# Pixie84Servo.net
KiCad netlist of a schematic drawn in EAGLE
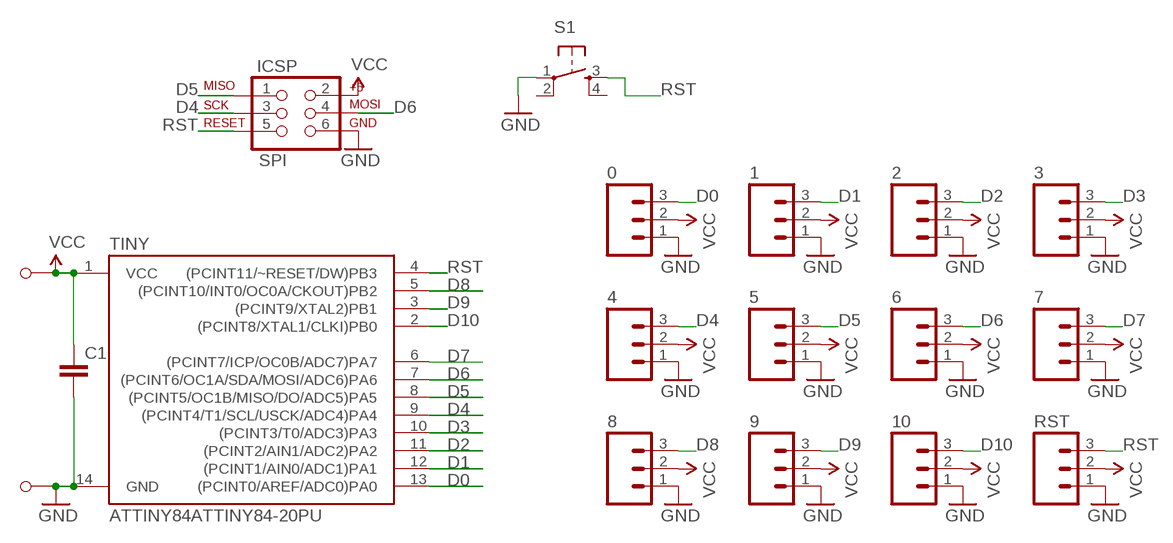
[diagram p0: schematic, sheet 1]

(export (version "E")
  (design (tool "Eeschema 10.0.6"))
  (components
    (comp (ref "0")
      (value "M03PTH")
      (footprint "eagle-import:1X03")
      (libsource (lib "eagle-import") (part "M03PTH"))
    )
    (comp (ref "1")
      (value "M03PTH")
      (footprint "eagle-import:1X03")
      (libsource (lib "eagle-import") (part "M03PTH"))
    )
    (comp (ref "2")
      (value "M03PTH")
      (footprint "eagle-import:1X03")
      (libsource (lib "eagle-import") (part "M03PTH"))
    )
    (comp (ref "3")
      (value "M03PTH")
      (footprint "eagle-import:1X03")
      (libsource (lib "eagle-import") (part "M03PTH"))
    )
    (comp (ref "4")
      (value "M03PTH")
      (footprint "eagle-import:1X03")
      (libsource (lib "eagle-import") (part "M03PTH"))
    )
    (comp (ref "5")
      (value "M03PTH")
      (footprint "eagle-import:1X03")
      (libsource (lib "eagle-import") (part "M03PTH"))
    )
    (comp (ref "6")
      (value "M03PTH")
      (footprint "eagle-import:1X03")
      (libsource (lib "eagle-import") (part "M03PTH"))
    )
    (comp (ref "7")
      (value "M03PTH")
      (footprint "eagle-import:1X03")
      (libsource (lib "eagle-import") (part "M03PTH"))
    )
    (comp (ref "8")
      (value "M03PTH")
      (footprint "eagle-import:1X03")
      (libsource (lib "eagle-import") (part "M03PTH"))
    )
    (comp (ref "9")
      (value "M03PTH")
      (footprint "eagle-import:1X03")
      (libsource (lib "eagle-import") (part "M03PTH"))
    )
    (comp (ref "10")
      (value "M03PTH")
      (footprint "eagle-import:1X03")
      (libsource (lib "eagle-import") (part "M03PTH"))
    )
    (comp (ref "C1")
      (value "CAPPTH")
      (footprint "eagle-import:CAP-PTH-SMALL")
      (libsource (lib "eagle-import") (part "CAPPTH"))
    )
    (comp (ref "ICSP")
      (value "SPI")
      (footprint "eagle-import:2X3-NS")
      (libsource (lib "eagle-import") (part "AVR_SPI_PRG_6LABELED"))
    )
    (comp (ref "RST")
      (value "M03PTH")
      (footprint "eagle-import:1X03")
      (libsource (lib "eagle-import") (part "M03PTH"))
    )
    (comp (ref "S1")
      (value "TAC_SWITCHPTH")
      (footprint "eagle-import:TACTILE-PTH")
      (libsource (lib "eagle-import") (part "TAC_SWITCHPTH"))
    )
    (comp (ref "TINY")
      (value "ATTINY84ATTINY84-20PU")
      (footprint "eagle-import:DIL14")
      (libsource (lib "eagle-import") (part "ATTINY84ATTINY84-20PU"))
    )
    (comp (ref "U$1")
      (value "M1")
      (footprint "eagle-import:M1_NO_STRAIN")
      (libsource (lib "eagle-import") (part "M1"))
    )
    (comp (ref "U$2")
      (value "M1")
      (footprint "eagle-import:M1_NO_STRAIN")
      (libsource (lib "eagle-import") (part "M1"))
    )
  )
  (nets
    (net (code "1") (name "/D0") (class "Default")
      (node (ref "0") (pin "3") (pinfunction "3_3") (pintype "passive"))
      (node (ref "TINY") (pin "13") (pinfunction "(PCINT0/AREF/ADC0)PA0_13") (pintype "bidirectional"))
    )
    (net (code "2") (name "/D1") (class "Default")
      (node (ref "1") (pin "3") (pinfunction "3_3") (pintype "passive"))
      (node (ref "TINY") (pin "12") (pinfunction "(PCINT1/AIN0/ADC1)PA1_12") (pintype "bidirectional"))
    )
    (net (code "3") (name "/D2") (class "Default")
      (node (ref "2") (pin "3") (pinfunction "3_3") (pintype "passive"))
      (node (ref "TINY") (pin "11") (pinfunction "(PCINT2/AIN1/ADC2)PA2_11") (pintype "bidirectional"))
    )
    (net (code "4") (name "/D3") (class "Default")
      (node (ref "3") (pin "3") (pinfunction "3_3") (pintype "passive"))
      (node (ref "TINY") (pin "10") (pinfunction "(PCINT3/T0/ADC3)PA3_10") (pintype "bidirectional"))
    )
    (net (code "5") (name "/D4") (class "Default")
      (node (ref "4") (pin "3") (pinfunction "3_3") (pintype "passive"))
      (node (ref "ICSP") (pin "3") (pinfunction "SCK_3") (pintype "passive"))
      (node (ref "TINY") (pin "9") (pinfunction "(PCINT4/T1/SCL/USCK/ADC4)PA4_9") (pintype "bidirectional"))
    )
    (net (code "6") (name "/D5") (class "Default")
      (node (ref "5") (pin "3") (pinfunction "3_3") (pintype "passive"))
      (node (ref "ICSP") (pin "1") (pinfunction "MISO_1") (pintype "passive"))
      (node (ref "TINY") (pin "8") (pinfunction "(PCINT5/OC1B/MISO/DO/ADC5)PA5_8") (pintype "bidirectional"))
    )
    (net (code "7") (name "/D6") (class "Default")
      (node (ref "6") (pin "3") (pinfunction "3_3") (pintype "passive"))
      (node (ref "ICSP") (pin "4") (pinfunction "MOSI_4") (pintype "passive"))
      (node (ref "TINY") (pin "7") (pinfunction "(PCINT6/OC1A/SDA/MOSI/ADC6)PA6_7") (pintype "bidirectional"))
    )
    (net (code "8") (name "/D7") (class "Default")
      (node (ref "7") (pin "3") (pinfunction "3_3") (pintype "passive"))
      (node (ref "TINY") (pin "6") (pinfunction "(PCINT7/ICP/OC0B/ADC7)PA7_6") (pintype "bidirectional"))
    )
    (net (code "9") (name "/D8") (class "Default")
      (node (ref "8") (pin "3") (pinfunction "3_3") (pintype "passive"))
      (node (ref "TINY") (pin "5") (pinfunction "(PCINT10/INT0/OC0A/CKOUT)PB2_5") (pintype "bidirectional"))
    )
    (net (code "10") (name "/D9") (class "Default")
      (node (ref "9") (pin "3") (pinfunction "3_3") (pintype "passive"))
      (node (ref "TINY") (pin "3") (pinfunction "(PCINT9/XTAL2)PB1_3") (pintype "bidirectional"))
    )
    (net (code "11") (name "/D10") (class "Default")
      (node (ref "10") (pin "3") (pinfunction "3_3") (pintype "passive"))
      (node (ref "TINY") (pin "2") (pinfunction "(PCINT8/XTAL1/CLKI)PB0_2") (pintype "bidirectional"))
    )
    (net (code "12") (name "/RST") (class "Default")
      (node (ref "ICSP") (pin "5") (pinfunction "RST_5") (pintype "passive"))
      (node (ref "RST") (pin "3") (pinfunction "3_3") (pintype "passive"))
      (node (ref "S1") (pin "3") (pinfunction "3_3") (pintype "passive"))
      (node (ref "TINY") (pin "4") (pinfunction "(PCINT11/~{RESET/DW})PB3_4") (pintype "bidirectional"))
    )
    (net (code "13") (name "GND") (class "Default")
      (node (ref "0") (pin "1") (pinfunction "1_1") (pintype "passive"))
      (node (ref "1") (pin "1") (pinfunction "1_1") (pintype "passive"))
      (node (ref "10") (pin "1") (pinfunction "1_1") (pintype "passive"))
      (node (ref "2") (pin "1") (pinfunction "1_1") (pintype "passive"))
      (node (ref "3") (pin "1") (pinfunction "1_1") (pintype "passive"))
      (node (ref "4") (pin "1") (pinfunction "1_1") (pintype "passive"))
      (node (ref "5") (pin "1") (pinfunction "1_1") (pintype "passive"))
      (node (ref "6") (pin "1") (pinfunction "1_1") (pintype "passive"))
      (node (ref "7") (pin "1") (pinfunction "1_1") (pintype "passive"))
      (node (ref "8") (pin "1") (pinfunction "1_1") (pintype "passive"))
      (node (ref "9") (pin "1") (pinfunction "1_1") (pintype "passive"))
      (node (ref "C1") (pin "2") (pinfunction "2_2") (pintype "passive"))
      (node (ref "ICSP") (pin "6") (pinfunction "GND_6") (pintype "passive"))
      (node (ref "RST") (pin "1") (pinfunction "1_1") (pintype "passive"))
      (node (ref "S1") (pin "1") (pinfunction "1_1") (pintype "passive"))
      (node (ref "TINY") (pin "14") (pinfunction "GND_14") (pintype "bidirectional"))
      (node (ref "U$2") (pin "P$1") (pinfunction "P$1_P$1") (pintype "bidirectional"))
    )
    (net (code "14") (name "VCC") (class "Default")
      (node (ref "0") (pin "2") (pinfunction "2_2") (pintype "passive"))
      (node (ref "1") (pin "2") (pinfunction "2_2") (pintype "passive"))
      (node (ref "10") (pin "2") (pinfunction "2_2") (pintype "passive"))
      (node (ref "2") (pin "2") (pinfunction "2_2") (pintype "passive"))
      (node (ref "3") (pin "2") (pinfunction "2_2") (pintype "passive"))
      (node (ref "4") (pin "2") (pinfunction "2_2") (pintype "passive"))
      (node (ref "5") (pin "2") (pinfunction "2_2") (pintype "passive"))
      (node (ref "6") (pin "2") (pinfunction "2_2") (pintype "passive"))
      (node (ref "7") (pin "2") (pinfunction "2_2") (pintype "passive"))
      (node (ref "8") (pin "2") (pinfunction "2_2") (pintype "passive"))
      (node (ref "9") (pin "2") (pinfunction "2_2") (pintype "passive"))
      (node (ref "C1") (pin "1") (pinfunction "1_1") (pintype "passive"))
      (node (ref "ICSP") (pin "2") (pinfunction "V+_2") (pintype "passive"))
      (node (ref "RST") (pin "2") (pinfunction "2_2") (pintype "passive"))
      (node (ref "TINY") (pin "1") (pinfunction "VCC_1") (pintype "bidirectional"))
      (node (ref "U$1") (pin "P$1") (pinfunction "P$1_P$1") (pintype "bidirectional"))
    )
    (net (code "15") (name "unconnected-(S1-Pad2)") (class "Default")
      (node (ref "S1") (pin "2") (pinfunction "2_2") (pintype "passive"))
    )
    (net (code "16") (name "unconnected-(S1-Pad4)") (class "Default")
      (node (ref "S1") (pin "4") (pinfunction "4_4") (pintype "passive"))
    )
  )
)
